# VFD_Board_V2.net
KiCad netlist of a schematic drawn in EAGLE
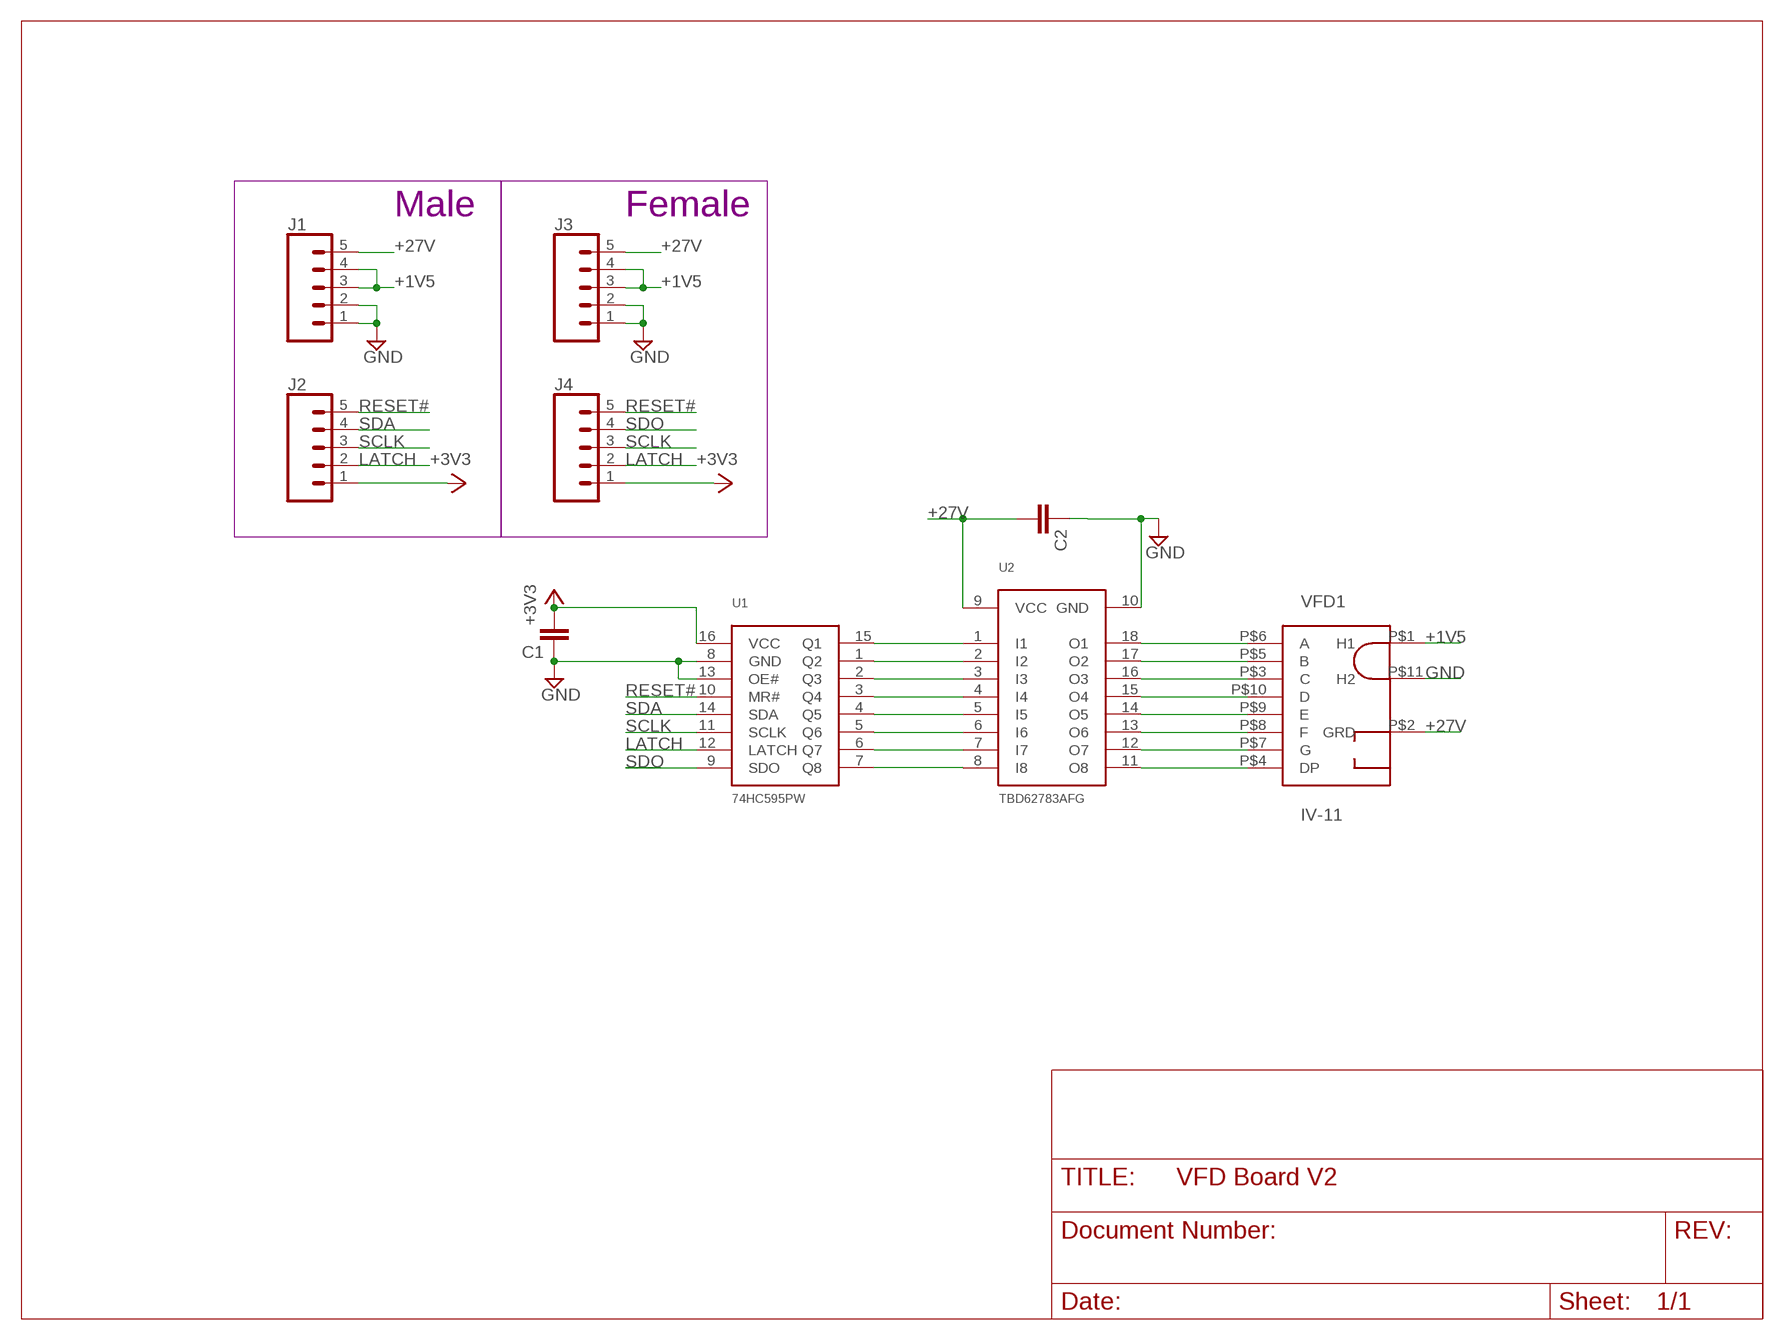
[diagram p0: schematic, sheet 1]

(export (version "E")
  (design (tool "Eeschema 10.0.6"))
  (components
    (comp (ref "C1")
      (value "C-EUC0603")
      (footprint "eagle-import:C0603")
      (libsource (lib "eagle-import") (part "C-EUC0603"))
    )
    (comp (ref "C2")
      (value "C-EUC0603")
      (footprint "eagle-import:C0603")
      (libsource (lib "eagle-import") (part "C-EUC0603"))
    )
    (comp (ref "J1")
      (value "CONN_05NO_SILK")
      (footprint "eagle-import:1X05_NO_SILK")
      (libsource (lib "eagle-import") (part "CONN_05NO_SILK"))
    )
    (comp (ref "J2")
      (value "CONN_05NO_SILK")
      (footprint "eagle-import:1X05_NO_SILK")
      (libsource (lib "eagle-import") (part "CONN_05NO_SILK"))
    )
    (comp (ref "J3")
      (value "CONN_05NO_SILK")
      (footprint "eagle-import:1X05_NO_SILK")
      (libsource (lib "eagle-import") (part "CONN_05NO_SILK"))
    )
    (comp (ref "J4")
      (value "CONN_05NO_SILK")
      (footprint "eagle-import:1X05_NO_SILK")
      (libsource (lib "eagle-import") (part "CONN_05NO_SILK"))
    )
    (comp (ref "U1")
      (value "74HC595PW")
      (footprint "eagle-import:TSSOP16")
      (libsource (lib "eagle-import") (part "74HC595PW"))
    )
    (comp (ref "U2")
      (value "TBD62783AFG")
      (footprint "eagle-import:SOIC18L")
      (libsource (lib "eagle-import") (part "TBD62783AFG"))
    )
    (comp (ref "VFD1")
      (value "IV-11")
      (footprint "eagle-import:IV-11")
      (libsource (lib "eagle-import") (part "IV-11"))
    )
  )
  (nets
    (net (code "1") (name "+3V3") (class "Default")
      (node (ref "C1") (pin "2") (pinfunction "2_2") (pintype "passive"))
      (node (ref "J2") (pin "1") (pinfunction "1_1") (pintype "passive"))
      (node (ref "J4") (pin "1") (pinfunction "1_1") (pintype "passive"))
      (node (ref "U1") (pin "16") (pinfunction "VCC_16") (pintype "bidirectional"))
    )
    (net (code "2") (name "/+1V5") (class "Default")
      (node (ref "J1") (pin "3") (pinfunction "3_3") (pintype "passive"))
      (node (ref "J1") (pin "4") (pinfunction "4_4") (pintype "passive"))
      (node (ref "J3") (pin "3") (pinfunction "3_3") (pintype "passive"))
      (node (ref "J3") (pin "4") (pinfunction "4_4") (pintype "passive"))
      (node (ref "VFD1") (pin "P$1") (pinfunction "H1_P$1") (pintype "bidirectional"))
    )
    (net (code "3") (name "/+27V") (class "Default")
      (node (ref "C2") (pin "2") (pinfunction "2_2") (pintype "passive"))
      (node (ref "J1") (pin "5") (pinfunction "5_5") (pintype "passive"))
      (node (ref "J3") (pin "5") (pinfunction "5_5") (pintype "passive"))
      (node (ref "U2") (pin "9") (pinfunction "VCC_9") (pintype "bidirectional"))
      (node (ref "VFD1") (pin "P$2") (pinfunction "GRD_P$2") (pintype "bidirectional"))
    )
    (net (code "4") (name "/LATCH") (class "Default")
      (node (ref "J2") (pin "2") (pinfunction "2_2") (pintype "passive"))
      (node (ref "J4") (pin "2") (pinfunction "2_2") (pintype "passive"))
      (node (ref "U1") (pin "12") (pinfunction "LATCH_12") (pintype "bidirectional"))
    )
    (net (code "5") (name "/RESET#") (class "Default")
      (node (ref "J2") (pin "5") (pinfunction "5_5") (pintype "passive"))
      (node (ref "J4") (pin "5") (pinfunction "5_5") (pintype "passive"))
      (node (ref "U1") (pin "10") (pinfunction "MR#_10") (pintype "bidirectional"))
    )
    (net (code "6") (name "/SCLK") (class "Default")
      (node (ref "J2") (pin "3") (pinfunction "3_3") (pintype "passive"))
      (node (ref "J4") (pin "3") (pinfunction "3_3") (pintype "passive"))
      (node (ref "U1") (pin "11") (pinfunction "SCLK_11") (pintype "bidirectional"))
    )
    (net (code "7") (name "/SDA") (class "Default")
      (node (ref "J2") (pin "4") (pinfunction "4_4") (pintype "passive"))
      (node (ref "U1") (pin "14") (pinfunction "SDA_14") (pintype "bidirectional"))
    )
    (net (code "8") (name "/SDO") (class "Default")
      (node (ref "J4") (pin "4") (pinfunction "4_4") (pintype "passive"))
      (node (ref "U1") (pin "9") (pinfunction "SDO_9") (pintype "bidirectional"))
    )
    (net (code "9") (name "GND") (class "Default")
      (node (ref "C1") (pin "1") (pinfunction "1_1") (pintype "passive"))
      (node (ref "C2") (pin "1") (pinfunction "1_1") (pintype "passive"))
      (node (ref "J1") (pin "1") (pinfunction "1_1") (pintype "passive"))
      (node (ref "J1") (pin "2") (pinfunction "2_2") (pintype "passive"))
      (node (ref "J3") (pin "1") (pinfunction "1_1") (pintype "passive"))
      (node (ref "J3") (pin "2") (pinfunction "2_2") (pintype "passive"))
      (node (ref "U1") (pin "13") (pinfunction "OE#_13") (pintype "bidirectional"))
      (node (ref "U1") (pin "8") (pinfunction "GND_8") (pintype "bidirectional"))
      (node (ref "U2") (pin "10") (pinfunction "GND_10") (pintype "bidirectional"))
      (node (ref "VFD1") (pin "P$11") (pinfunction "H2_P$11") (pintype "bidirectional"))
    )
    (net (code "10") (name "Net-(U1-Q1)") (class "Default")
      (node (ref "U1") (pin "15") (pinfunction "Q1_15") (pintype "bidirectional"))
      (node (ref "U2") (pin "1") (pinfunction "I1_1") (pintype "bidirectional"))
    )
    (net (code "11") (name "Net-(U1-Q2)") (class "Default")
      (node (ref "U1") (pin "1") (pinfunction "Q2_1") (pintype "bidirectional"))
      (node (ref "U2") (pin "2") (pinfunction "I2_2") (pintype "bidirectional"))
    )
    (net (code "12") (name "Net-(U1-Q3)") (class "Default")
      (node (ref "U1") (pin "2") (pinfunction "Q3_2") (pintype "bidirectional"))
      (node (ref "U2") (pin "3") (pinfunction "I3_3") (pintype "bidirectional"))
    )
    (net (code "13") (name "Net-(U1-Q4)") (class "Default")
      (node (ref "U1") (pin "3") (pinfunction "Q4_3") (pintype "bidirectional"))
      (node (ref "U2") (pin "4") (pinfunction "I4_4") (pintype "bidirectional"))
    )
    (net (code "14") (name "Net-(U1-Q5)") (class "Default")
      (node (ref "U1") (pin "4") (pinfunction "Q5_4") (pintype "bidirectional"))
      (node (ref "U2") (pin "5") (pinfunction "I5_5") (pintype "bidirectional"))
    )
    (net (code "15") (name "Net-(U1-Q6)") (class "Default")
      (node (ref "U1") (pin "5") (pinfunction "Q6_5") (pintype "bidirectional"))
      (node (ref "U2") (pin "6") (pinfunction "I6_6") (pintype "bidirectional"))
    )
    (net (code "16") (name "Net-(U1-Q7)") (class "Default")
      (node (ref "U1") (pin "6") (pinfunction "Q7_6") (pintype "bidirectional"))
      (node (ref "U2") (pin "7") (pinfunction "I7_7") (pintype "bidirectional"))
    )
    (net (code "17") (name "Net-(U1-Q8)") (class "Default")
      (node (ref "U1") (pin "7") (pinfunction "Q8_7") (pintype "bidirectional"))
      (node (ref "U2") (pin "8") (pinfunction "I8_8") (pintype "bidirectional"))
    )
    (net (code "18") (name "Net-(U2-O1)") (class "Default")
      (node (ref "U2") (pin "18") (pinfunction "O1_18") (pintype "bidirectional"))
      (node (ref "VFD1") (pin "P$6") (pinfunction "A_P$6") (pintype "bidirectional"))
    )
    (net (code "19") (name "Net-(U2-O2)") (class "Default")
      (node (ref "U2") (pin "17") (pinfunction "O2_17") (pintype "bidirectional"))
      (node (ref "VFD1") (pin "P$5") (pinfunction "B_P$5") (pintype "bidirectional"))
    )
    (net (code "20") (name "Net-(U2-O3)") (class "Default")
      (node (ref "U2") (pin "16") (pinfunction "O3_16") (pintype "bidirectional"))
      (node (ref "VFD1") (pin "P$3") (pinfunction "C_P$3") (pintype "bidirectional"))
    )
    (net (code "21") (name "Net-(U2-O4)") (class "Default")
      (node (ref "U2") (pin "15") (pinfunction "O4_15") (pintype "bidirectional"))
      (node (ref "VFD1") (pin "P$10") (pinfunction "D_P$10") (pintype "bidirectional"))
    )
    (net (code "22") (name "Net-(U2-O5)") (class "Default")
      (node (ref "U2") (pin "14") (pinfunction "O5_14") (pintype "bidirectional"))
      (node (ref "VFD1") (pin "P$9") (pinfunction "E_P$9") (pintype "bidirectional"))
    )
    (net (code "23") (name "Net-(U2-O6)") (class "Default")
      (node (ref "U2") (pin "13") (pinfunction "O6_13") (pintype "bidirectional"))
      (node (ref "VFD1") (pin "P$8") (pinfunction "F_P$8") (pintype "bidirectional"))
    )
    (net (code "24") (name "Net-(U2-O7)") (class "Default")
      (node (ref "U2") (pin "12") (pinfunction "O7_12") (pintype "bidirectional"))
      (node (ref "VFD1") (pin "P$7") (pinfunction "G_P$7") (pintype "bidirectional"))
    )
    (net (code "25") (name "Net-(U2-O8)") (class "Default")
      (node (ref "U2") (pin "11") (pinfunction "O8_11") (pintype "bidirectional"))
      (node (ref "VFD1") (pin "P$4") (pinfunction "DP_P$4") (pintype "bidirectional"))
    )
  )
)
